# BATT_FLEXX.net
KiCad netlist of a schematic drawn in EAGLE
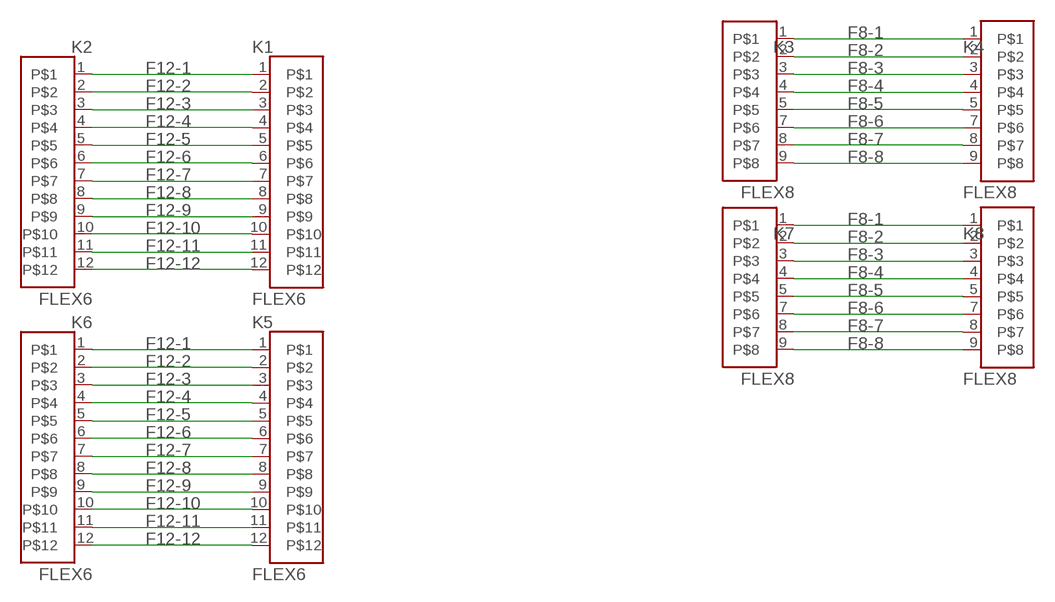
[diagram p0: schematic, sheet 1]

(export (version "E")
  (design (tool "Eeschema 10.0.6"))
  (components
    (comp (ref "K1")
      (value "FLEX6")
      (footprint "eagle-import:FLEX6")
      (libsource (lib "eagle-import") (part "FLEX6"))
    )
    (comp (ref "K2")
      (value "FLEX6")
      (footprint "eagle-import:FLEX6")
      (libsource (lib "eagle-import") (part "FLEX6"))
    )
    (comp (ref "K3")
      (value "FLEX8")
      (footprint "eagle-import:FLEX8")
      (libsource (lib "eagle-import") (part "FLEX8"))
    )
    (comp (ref "K4")
      (value "FLEX8")
      (footprint "eagle-import:FLEX8")
      (libsource (lib "eagle-import") (part "FLEX8"))
    )
    (comp (ref "K5")
      (value "FLEX6")
      (footprint "eagle-import:FLEX6")
      (libsource (lib "eagle-import") (part "FLEX6"))
    )
    (comp (ref "K6")
      (value "FLEX6")
      (footprint "eagle-import:FLEX6")
      (libsource (lib "eagle-import") (part "FLEX6"))
    )
    (comp (ref "K7")
      (value "FLEX8")
      (footprint "eagle-import:FLEX8")
      (libsource (lib "eagle-import") (part "FLEX8"))
    )
    (comp (ref "K8")
      (value "FLEX8")
      (footprint "eagle-import:FLEX8")
      (libsource (lib "eagle-import") (part "FLEX8"))
    )
  )
  (nets
    (net (code "1") (name "/F8-1") (class "Default")
      (node (ref "K3") (pin "1") (pinfunction "P$1_1") (pintype "bidirectional"))
      (node (ref "K4") (pin "1") (pinfunction "P$1_1") (pintype "bidirectional"))
      (node (ref "K7") (pin "1") (pinfunction "P$1_1") (pintype "bidirectional"))
      (node (ref "K8") (pin "1") (pinfunction "P$1_1") (pintype "bidirectional"))
    )
    (net (code "2") (name "/F8-2") (class "Default")
      (node (ref "K3") (pin "2") (pinfunction "P$2_2") (pintype "bidirectional"))
      (node (ref "K4") (pin "2") (pinfunction "P$2_2") (pintype "bidirectional"))
      (node (ref "K7") (pin "2") (pinfunction "P$2_2") (pintype "bidirectional"))
      (node (ref "K8") (pin "2") (pinfunction "P$2_2") (pintype "bidirectional"))
    )
    (net (code "3") (name "/F8-3") (class "Default")
      (node (ref "K3") (pin "3") (pinfunction "P$3_3") (pintype "bidirectional"))
      (node (ref "K4") (pin "3") (pinfunction "P$3_3") (pintype "bidirectional"))
      (node (ref "K7") (pin "3") (pinfunction "P$3_3") (pintype "bidirectional"))
      (node (ref "K8") (pin "3") (pinfunction "P$3_3") (pintype "bidirectional"))
    )
    (net (code "4") (name "/F8-4") (class "Default")
      (node (ref "K3") (pin "4") (pinfunction "P$4_4") (pintype "bidirectional"))
      (node (ref "K4") (pin "4") (pinfunction "P$4_4") (pintype "bidirectional"))
      (node (ref "K7") (pin "4") (pinfunction "P$4_4") (pintype "bidirectional"))
      (node (ref "K8") (pin "4") (pinfunction "P$4_4") (pintype "bidirectional"))
    )
    (net (code "5") (name "/F8-5") (class "Default")
      (node (ref "K3") (pin "5") (pinfunction "P$5_5") (pintype "bidirectional"))
      (node (ref "K4") (pin "5") (pinfunction "P$5_5") (pintype "bidirectional"))
      (node (ref "K7") (pin "5") (pinfunction "P$5_5") (pintype "bidirectional"))
      (node (ref "K8") (pin "5") (pinfunction "P$5_5") (pintype "bidirectional"))
    )
    (net (code "6") (name "/F8-6") (class "Default")
      (node (ref "K3") (pin "7") (pinfunction "P$6_7") (pintype "bidirectional"))
      (node (ref "K4") (pin "7") (pinfunction "P$6_7") (pintype "bidirectional"))
      (node (ref "K7") (pin "7") (pinfunction "P$6_7") (pintype "bidirectional"))
      (node (ref "K8") (pin "7") (pinfunction "P$6_7") (pintype "bidirectional"))
    )
    (net (code "7") (name "/F8-7") (class "Default")
      (node (ref "K3") (pin "8") (pinfunction "P$7_8") (pintype "bidirectional"))
      (node (ref "K4") (pin "8") (pinfunction "P$7_8") (pintype "bidirectional"))
      (node (ref "K7") (pin "8") (pinfunction "P$7_8") (pintype "bidirectional"))
      (node (ref "K8") (pin "8") (pinfunction "P$7_8") (pintype "bidirectional"))
    )
    (net (code "8") (name "/F8-8") (class "Default")
      (node (ref "K3") (pin "9") (pinfunction "P$8_9") (pintype "bidirectional"))
      (node (ref "K4") (pin "9") (pinfunction "P$8_9") (pintype "bidirectional"))
      (node (ref "K7") (pin "9") (pinfunction "P$8_9") (pintype "bidirectional"))
      (node (ref "K8") (pin "9") (pinfunction "P$8_9") (pintype "bidirectional"))
    )
    (net (code "9") (name "/F12-1") (class "Default")
      (node (ref "K1") (pin "1") (pinfunction "P$1_1") (pintype "bidirectional"))
      (node (ref "K2") (pin "1") (pinfunction "P$1_1") (pintype "bidirectional"))
      (node (ref "K5") (pin "1") (pinfunction "P$1_1") (pintype "bidirectional"))
      (node (ref "K6") (pin "1") (pinfunction "P$1_1") (pintype "bidirectional"))
    )
    (net (code "10") (name "/F12-2") (class "Default")
      (node (ref "K1") (pin "2") (pinfunction "P$2_2") (pintype "bidirectional"))
      (node (ref "K2") (pin "2") (pinfunction "P$2_2") (pintype "bidirectional"))
      (node (ref "K5") (pin "2") (pinfunction "P$2_2") (pintype "bidirectional"))
      (node (ref "K6") (pin "2") (pinfunction "P$2_2") (pintype "bidirectional"))
    )
    (net (code "11") (name "/F12-3") (class "Default")
      (node (ref "K1") (pin "3") (pinfunction "P$3_3") (pintype "bidirectional"))
      (node (ref "K2") (pin "3") (pinfunction "P$3_3") (pintype "bidirectional"))
      (node (ref "K5") (pin "3") (pinfunction "P$3_3") (pintype "bidirectional"))
      (node (ref "K6") (pin "3") (pinfunction "P$3_3") (pintype "bidirectional"))
    )
    (net (code "12") (name "/F12-4") (class "Default")
      (node (ref "K1") (pin "4") (pinfunction "P$4_4") (pintype "bidirectional"))
      (node (ref "K2") (pin "4") (pinfunction "P$4_4") (pintype "bidirectional"))
      (node (ref "K5") (pin "4") (pinfunction "P$4_4") (pintype "bidirectional"))
      (node (ref "K6") (pin "4") (pinfunction "P$4_4") (pintype "bidirectional"))
    )
    (net (code "13") (name "/F12-5") (class "Default")
      (node (ref "K1") (pin "5") (pinfunction "P$5_5") (pintype "bidirectional"))
      (node (ref "K2") (pin "5") (pinfunction "P$5_5") (pintype "bidirectional"))
      (node (ref "K5") (pin "5") (pinfunction "P$5_5") (pintype "bidirectional"))
      (node (ref "K6") (pin "5") (pinfunction "P$5_5") (pintype "bidirectional"))
    )
    (net (code "14") (name "/F12-6") (class "Default")
      (node (ref "K1") (pin "6") (pinfunction "P$6_6") (pintype "bidirectional"))
      (node (ref "K2") (pin "6") (pinfunction "P$6_6") (pintype "bidirectional"))
      (node (ref "K5") (pin "6") (pinfunction "P$6_6") (pintype "bidirectional"))
      (node (ref "K6") (pin "6") (pinfunction "P$6_6") (pintype "bidirectional"))
    )
    (net (code "15") (name "/F12-7") (class "Default")
      (node (ref "K1") (pin "7") (pinfunction "P$7_7") (pintype "bidirectional"))
      (node (ref "K2") (pin "7") (pinfunction "P$7_7") (pintype "bidirectional"))
      (node (ref "K5") (pin "7") (pinfunction "P$7_7") (pintype "bidirectional"))
      (node (ref "K6") (pin "7") (pinfunction "P$7_7") (pintype "bidirectional"))
    )
    (net (code "16") (name "/F12-8") (class "Default")
      (node (ref "K1") (pin "8") (pinfunction "P$8_8") (pintype "bidirectional"))
      (node (ref "K2") (pin "8") (pinfunction "P$8_8") (pintype "bidirectional"))
      (node (ref "K5") (pin "8") (pinfunction "P$8_8") (pintype "bidirectional"))
      (node (ref "K6") (pin "8") (pinfunction "P$8_8") (pintype "bidirectional"))
    )
    (net (code "17") (name "/F12-9") (class "Default")
      (node (ref "K1") (pin "9") (pinfunction "P$9_9") (pintype "bidirectional"))
      (node (ref "K2") (pin "9") (pinfunction "P$9_9") (pintype "bidirectional"))
      (node (ref "K5") (pin "9") (pinfunction "P$9_9") (pintype "bidirectional"))
      (node (ref "K6") (pin "9") (pinfunction "P$9_9") (pintype "bidirectional"))
    )
    (net (code "18") (name "/F12-10") (class "Default")
      (node (ref "K1") (pin "10") (pinfunction "P$10_10") (pintype "bidirectional"))
      (node (ref "K2") (pin "10") (pinfunction "P$10_10") (pintype "bidirectional"))
      (node (ref "K5") (pin "10") (pinfunction "P$10_10") (pintype "bidirectional"))
      (node (ref "K6") (pin "10") (pinfunction "P$10_10") (pintype "bidirectional"))
    )
    (net (code "19") (name "/F12-11") (class "Default")
      (node (ref "K1") (pin "11") (pinfunction "P$11_11") (pintype "bidirectional"))
      (node (ref "K2") (pin "11") (pinfunction "P$11_11") (pintype "bidirectional"))
      (node (ref "K5") (pin "11") (pinfunction "P$11_11") (pintype "bidirectional"))
      (node (ref "K6") (pin "11") (pinfunction "P$11_11") (pintype "bidirectional"))
    )
    (net (code "20") (name "/F12-12") (class "Default")
      (node (ref "K1") (pin "12") (pinfunction "P$12_12") (pintype "bidirectional"))
      (node (ref "K2") (pin "12") (pinfunction "P$12_12") (pintype "bidirectional"))
      (node (ref "K5") (pin "12") (pinfunction "P$12_12") (pintype "bidirectional"))
      (node (ref "K6") (pin "12") (pinfunction "P$12_12") (pintype "bidirectional"))
    )
  )
)
